# SCH_miliohn_V_1_2026-03-07.net
KiCad netlist of a schematic drawn in EasyEDA
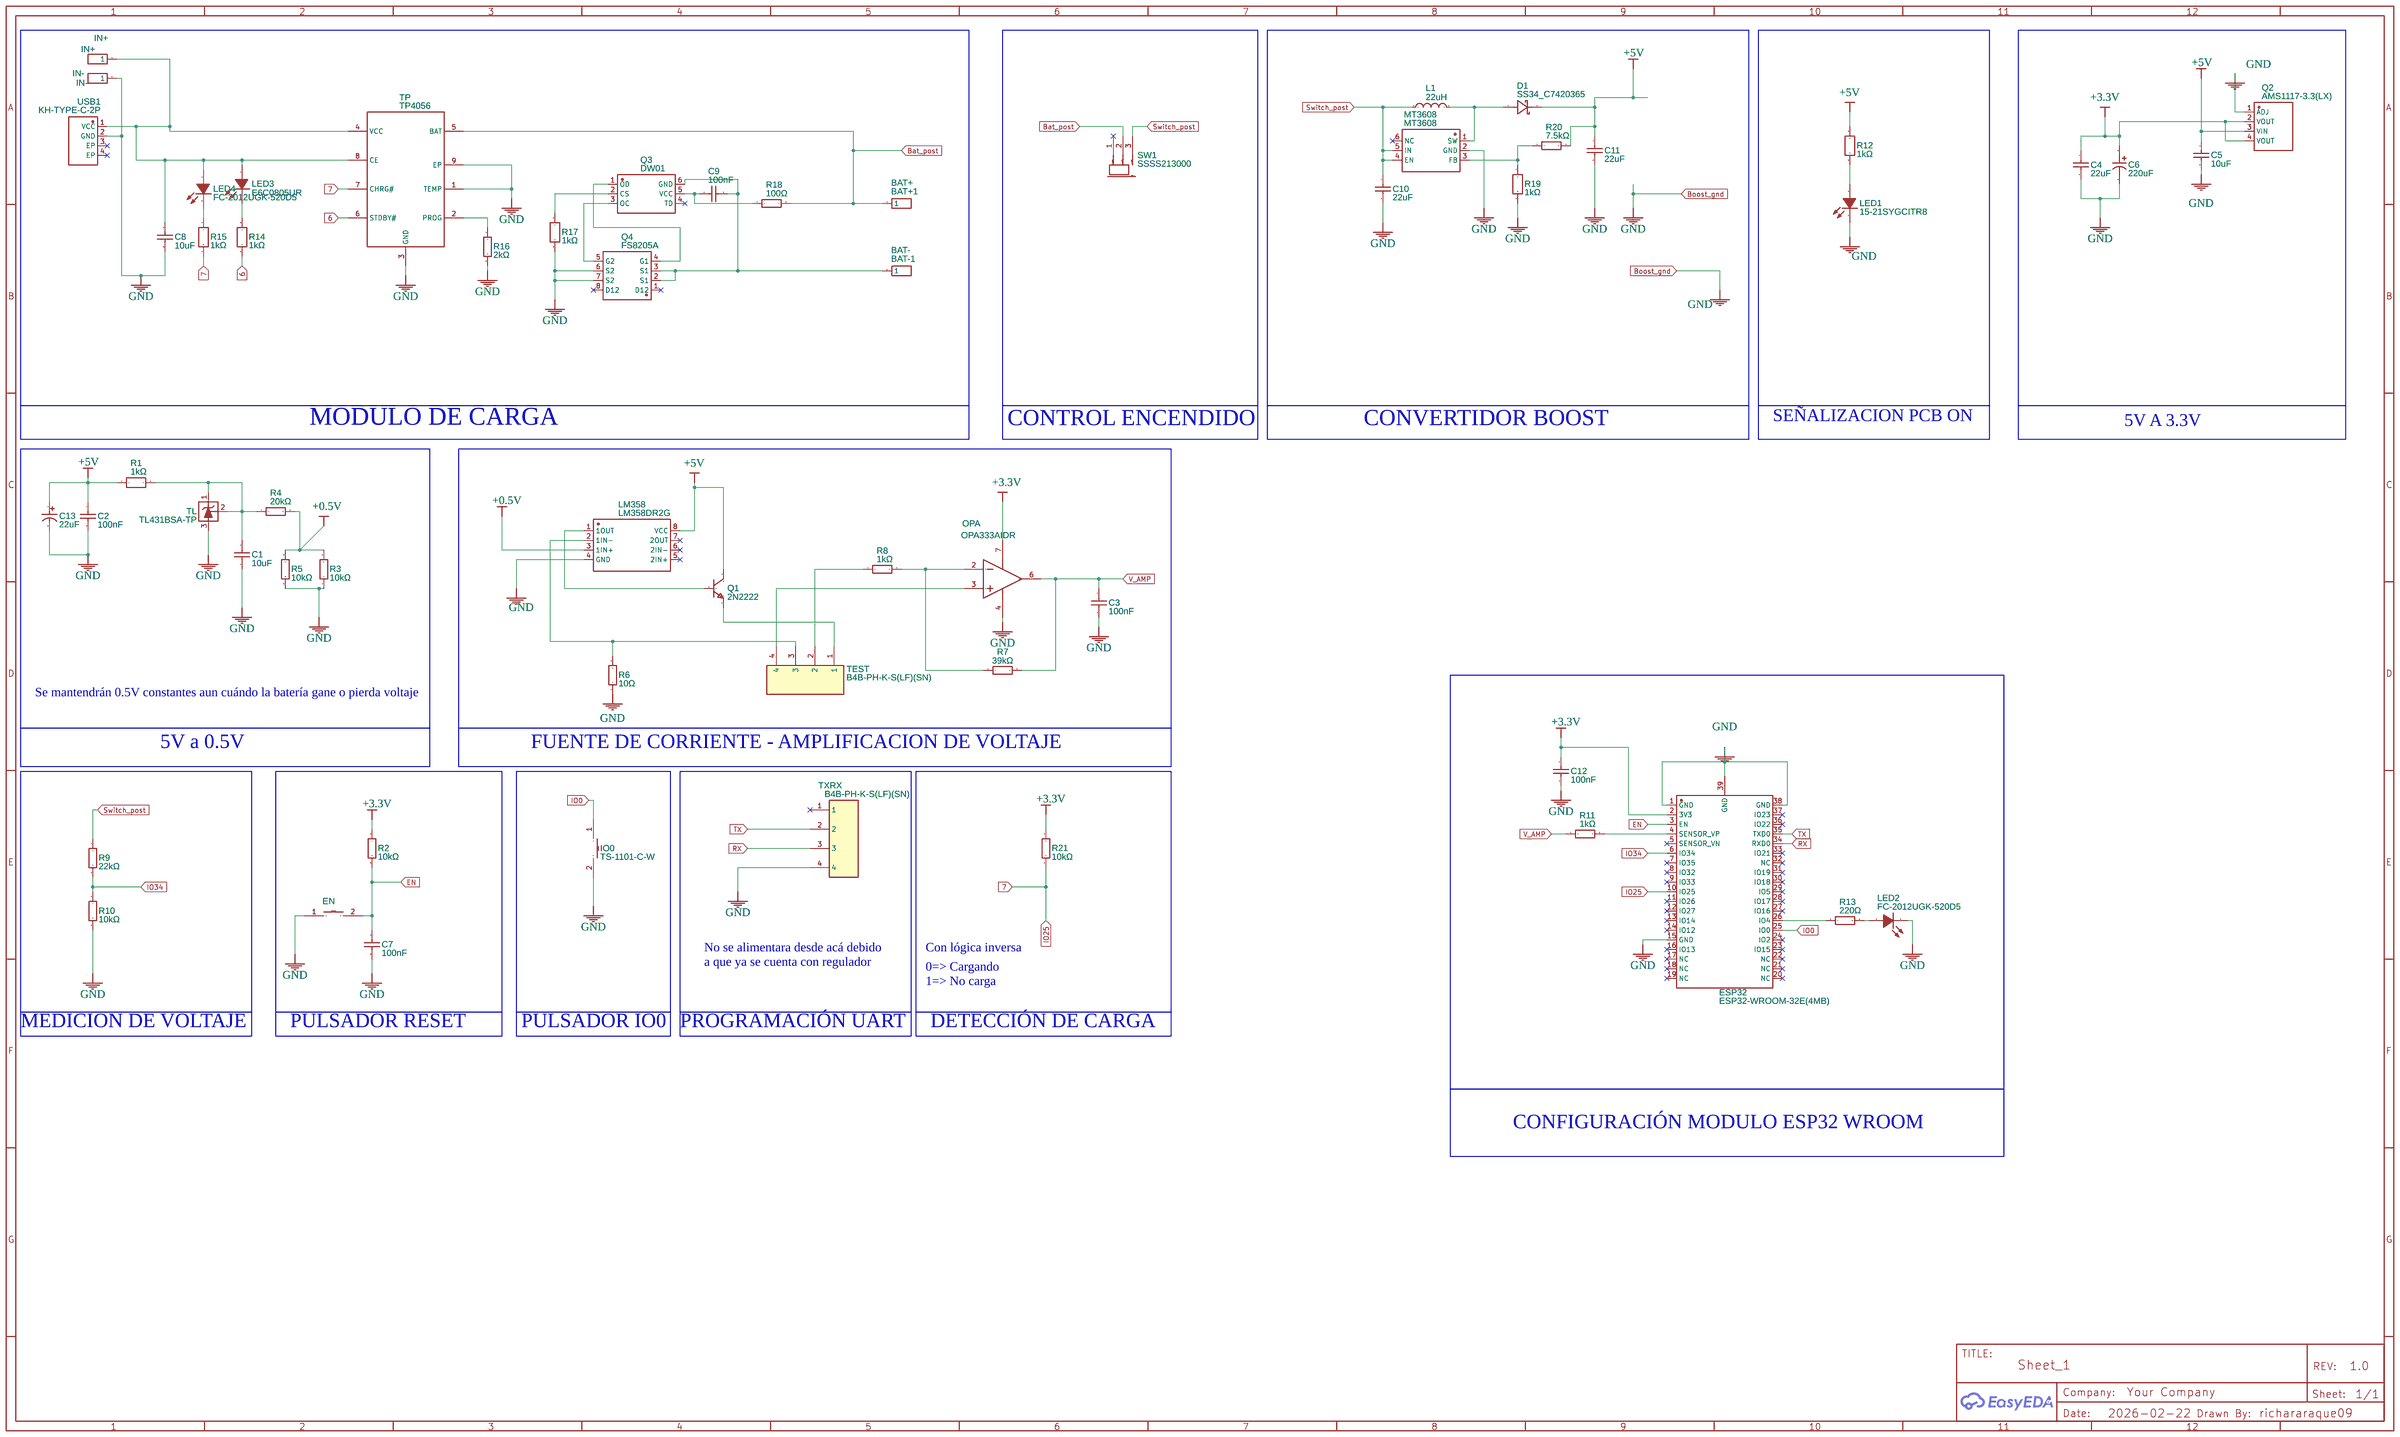
[diagram p0: schematic sheet]

(export (version "E")
  (design (tool "Eeschema 10.0.6"))
  (components
    (comp (ref "BAT+") (value "BAT+1") (libsource (lib "") (part "HDR-M-2.54_1x1_3")))
    (comp (ref "BAT-") (value "BAT-1") (libsource (lib "") (part "HDR-M-2.54_1x1")))
    (comp (ref "C1")
      (value "10uF")
      (fields
        (field (name "Manufacturer Part") "CL31A106KBHNNNE")
        (field (name "Manufacturer") "SAMSUNG(三星)")
      )
      (libsource (lib "") (part "CL31A106KBHNNNE"))
    )
    (comp (ref "C2")
      (value "100nF")
      (fields
        (field (name "Manufacturer Part") "CL31B104KBCNNNC")
        (field (name "Manufacturer") "SAMSUNG(三星)")
      )
      (libsource (lib "") (part "CL31B104KBCNNNC"))
    )
    (comp (ref "C3")
      (value "100nF")
      (fields
        (field (name "Manufacturer Part") "CL31B104KBCNNNC")
        (field (name "Manufacturer") "SAMSUNG(三星)")
      )
      (libsource (lib "") (part "CL31B104KBCNNNC"))
    )
    (comp (ref "C4")
      (value "22uF")
      (fields (field (name "Manufacturer Part") "1206X226K100NT") (field (name "Manufacturer") "FH(风华)"))
      (libsource (lib "") (part "1206X226K100NT"))
    )
    (comp (ref "C5")
      (value "10uF")
      (fields
        (field (name "Manufacturer Part") "CL31A106KBHNNNE")
        (field (name "Manufacturer") "SAMSUNG(三星)")
      )
      (libsource (lib "") (part "CL31A106KBHNNNE"))
    )
    (comp (ref "C6")
      (value "220uF")
      (fields
        (field (name "Manufacturer Part") "RVT1C221M0607 220UF 16V")
        (field (name "Manufacturer") "DMBJ(振宝佳)")
      )
      (libsource (lib "") (part "RVT1C221M0607 220UF 16V"))
    )
    (comp (ref "C7")
      (value "100nF")
      (fields
        (field (name "Manufacturer Part") "CL31B104KBCNNNC")
        (field (name "Manufacturer") "SAMSUNG(三星)")
      )
      (libsource (lib "") (part "CL31B104KBCNNNC"))
    )
    (comp (ref "C8")
      (value "10uF")
      (fields
        (field (name "Manufacturer Part") "CL31A106KBHNNNE")
        (field (name "Manufacturer") "SAMSUNG(三星)")
      )
      (libsource (lib "") (part "CL31A106KBHNNNE"))
    )
    (comp (ref "C9")
      (value "100nF")
      (fields
        (field (name "Manufacturer Part") "CL31B104KBCNNNC")
        (field (name "Manufacturer") "SAMSUNG(三星)")
      )
      (libsource (lib "") (part "CL31B104KBCNNNC_1"))
    )
    (comp (ref "C10")
      (value "22uF")
      (fields (field (name "Manufacturer Part") "1206X226K100NT") (field (name "Manufacturer") "FH(风华)"))
      (libsource (lib "") (part "1206X226K100NT"))
    )
    (comp (ref "C11")
      (value "22uF")
      (fields (field (name "Manufacturer Part") "1206X226K100NT") (field (name "Manufacturer") "FH(风华)"))
      (libsource (lib "") (part "1206X226K100NT"))
    )
    (comp (ref "C12")
      (value "100nF")
      (fields
        (field (name "Manufacturer Part") "CL31B104KBCNNNC")
        (field (name "Manufacturer") "SAMSUNG(三星)")
      )
      (libsource (lib "") (part "CL31B104KBCNNNC"))
    )
    (comp (ref "C13")
      (value "22uF")
      (fields (field (name "Manufacturer Part") "RVT1C220M0405") (field (name "Manufacturer") "HONOR(荣誉)"))
      (libsource (lib "") (part "RVT1C220M0405_C3356"))
    )
    (comp (ref "D1")
      (value "SS34_C7420365")
      (fields (field (name "Manufacturer Part") "SS34") (field (name "Manufacturer") "R+O(宏嘉诚)"))
      (libsource (lib "") (part "SS34_C7420365"))
    )
    (comp (ref "EN")
      (value "EN")
      (fields
        (field (name "Manufacturer Part") "TS-1101-C-W")
        (field (name "Manufacturer") "XKB Connectivity(中国星坤)")
      )
      (libsource (lib "") (part "TS-1101-C-W_1"))
    )
    (comp (ref "ESP32")
      (value "ESP32-WROOM-32E(4MB)")
      (fields
        (field (name "Manufacturer Part") "ESP32-WROOM-32E-N4")
        (field (name "Manufacturer") "ESPRESSIF(乐鑫)")
      )
      (libsource (lib "") (part "ESP32-WROOM-32E(4MB)"))
    )
    (comp (ref "IN+") (value "IN+") (libsource (lib "") (part "HDR-M-2.54_1x1_2")))
    (comp (ref "IN-") (value "IN-") (libsource (lib "") (part "HDR-M-2.54_1x1_1")))
    (comp (ref "IO0")
      (value "TS-1101-C-W")
      (fields (field (name "Manufacturer") "XKB Connectivity(中国星坤)"))
      (libsource (lib "") (part "TS-1101-C-W"))
    )
    (comp (ref "L1")
      (value "22uH")
      (fields (field (name "Manufacturer Part") "CD32-220K") (field (name "Manufacturer") "ceaiya(柯爱亚)"))
      (libsource (lib "") (part "CD32-220K"))
    )
    (comp (ref "LED1")
      (value "15-21SYGCITR8")
      (fields (field (name "Manufacturer Part") "KT-1206Y") (field (name "Manufacturer") "KENTO"))
      (libsource (lib "") (part "15-21SYGCITR8"))
    )
    (comp (ref "LED2")
      (value "FC-2012UGK-520D5")
      (fields (field (name "Manufacturer Part") "NCD0805G1") (field (name "Manufacturer") "国星光电"))
      (libsource (lib "") (part "FC-2012UGK-520D5"))
    )
    (comp (ref "LED3")
      (value "E6C0805UR")
      (fields (field (name "Manufacturer Part") "KT-0805R") (field (name "Manufacturer") "KENTO"))
      (libsource (lib "") (part "E6C0805UR"))
    )
    (comp (ref "LED4")
      (value "FC-2012UGK-520D5")
      (fields (field (name "Manufacturer Part") "NCD0805G1") (field (name "Manufacturer") "国星光电"))
      (libsource (lib "") (part "FC-2012UGK-520D5_1"))
    )
    (comp (ref "LM358")
      (value "LM358DR2G")
      (fields (field (name "Manufacturer") "onsemi(安森美)"))
      (libsource (lib "") (part "LM358DR2G"))
    )
    (comp (ref "MT3608")
      (value "MT3608")
      (fields (field (name "Manufacturer") "西安航天民芯"))
      (libsource (lib "") (part "MT3608"))
    )
    (comp (ref "OPA")
      (value "OPA333AIDR")
      (fields (field (name "Manufacturer") "TI(德州仪器)"))
      (libsource (lib "") (part "OPA333AIDR"))
    )
    (comp (ref "Q1")
      (value "2N2222")
      (fields (field (name "Manufacturer Part") "2N2222A") (field (name "Manufacturer") "ST(先科)"))
      (libsource (lib "") (part "2N2222"))
    )
    (comp (ref "Q2")
      (value "AMS1117-3.3(LX)")
      (fields (field (name "Manufacturer") "LX(灵星芯微)"))
      (libsource (lib "") (part "AMS1117-3.3(LX)"))
    )
    (comp (ref "Q3")
      (value "DW01")
      (fields (field (name "Manufacturer") "Hottech(合科泰)"))
      (libsource (lib "") (part "DW01"))
    )
    (comp (ref "Q4")
      (value "FS8205A")
      (fields (field (name "Manufacturer") "FORTUNE(富晶)"))
      (libsource (lib "") (part "FS8205A"))
    )
    (comp (ref "R1")
      (value "1kΩ")
      (fields (field (name "Manufacturer Part") "SCR1206J1K") (field (name "Manufacturer") "VO(翔胜)"))
      (libsource (lib "") (part "SCR1206J1K_1"))
    )
    (comp (ref "R2")
      (value "10kΩ")
      (fields
        (field (name "Manufacturer Part") "1206W4F1002T5E")
        (field (name "Manufacturer") "UNI-ROYAL(厚声)")
      )
      (libsource (lib "") (part "1206W4F1002T5E"))
    )
    (comp (ref "R3")
      (value "10kΩ")
      (fields
        (field (name "Manufacturer Part") "1206W4F1002T5E")
        (field (name "Manufacturer") "UNI-ROYAL(厚声)")
      )
      (libsource (lib "") (part "1206W4F1002T5E_1"))
    )
    (comp (ref "R4")
      (value "20kΩ")
      (fields
        (field (name "Manufacturer Part") "0805W8F2002T5E")
        (field (name "Manufacturer") "UNI-ROYAL(厚声)")
      )
      (libsource (lib "") (part "0805W8F2002T5E"))
    )
    (comp (ref "R5")
      (value "10kΩ")
      (fields
        (field (name "Manufacturer Part") "1206W4F1002T5E")
        (field (name "Manufacturer") "UNI-ROYAL(厚声)")
      )
      (libsource (lib "") (part "1206W4F1002T5E"))
    )
    (comp (ref "R6")
      (value "10Ω")
      (fields
        (field (name "Manufacturer Part") "1206W4F100JT5E")
        (field (name "Manufacturer") "UNI-ROYAL(厚声)")
      )
      (libsource (lib "") (part "1206W4F100JT5E"))
    )
    (comp (ref "R7")
      (value "39kΩ")
      (fields
        (field (name "Manufacturer Part") "1206W4F3902T5E")
        (field (name "Manufacturer") "UNI-ROYAL(厚声)")
      )
      (libsource (lib "") (part "1206W4F3902T5E"))
    )
    (comp (ref "R8")
      (value "1kΩ")
      (fields
        (field (name "Manufacturer Part") "1206W4J0102T5E")
        (field (name "Manufacturer") "UNI-ROYAL(厚声)")
      )
      (libsource (lib "") (part "1206W4J0102T5E"))
    )
    (comp (ref "R9")
      (value "22kΩ")
      (fields
        (field (name "Manufacturer Part") "1206W4F2202T5E")
        (field (name "Manufacturer") "UNI-ROYAL(厚声)")
      )
      (libsource (lib "") (part "1206W4F2202T5E"))
    )
    (comp (ref "R10")
      (value "10kΩ")
      (fields
        (field (name "Manufacturer Part") "1206W4F1002T5E")
        (field (name "Manufacturer") "UNI-ROYAL(厚声)")
      )
      (libsource (lib "") (part "1206W4F1002T5E"))
    )
    (comp (ref "R11")
      (value "1kΩ")
      (fields
        (field (name "Manufacturer Part") "1206W4J0102T5E")
        (field (name "Manufacturer") "UNI-ROYAL(厚声)")
      )
      (libsource (lib "") (part "1206W4J0102T5E"))
    )
    (comp (ref "R12")
      (value "1kΩ")
      (fields (field (name "Manufacturer Part") "SCR1206J1K") (field (name "Manufacturer") "VO(翔胜)"))
      (libsource (lib "") (part "SCR1206J1K_2"))
    )
    (comp (ref "R13")
      (value "220Ω")
      (fields
        (field (name "Manufacturer Part") "1206W4F2200T5E")
        (field (name "Manufacturer") "UNI-ROYAL(厚声)")
      )
      (libsource (lib "") (part "1206W4F2200T5E"))
    )
    (comp (ref "R14")
      (value "1kΩ")
      (fields (field (name "Manufacturer Part") "SCR1206J1K") (field (name "Manufacturer") "VO(翔胜)"))
      (libsource (lib "") (part "SCR1206J1K"))
    )
    (comp (ref "R15")
      (value "1kΩ")
      (fields (field (name "Manufacturer Part") "SCR1206J1K") (field (name "Manufacturer") "VO(翔胜)"))
      (libsource (lib "") (part "SCR1206J1K"))
    )
    (comp (ref "R16")
      (value "2kΩ")
      (fields
        (field (name "Manufacturer Part") "0805W8J0202T5E")
        (field (name "Manufacturer") "UNI-ROYAL(厚声)")
      )
      (libsource (lib "") (part "0805W8J0202T5E"))
    )
    (comp (ref "R17")
      (value "1kΩ")
      (fields (field (name "Manufacturer Part") "SCR1206J1K") (field (name "Manufacturer") "VO(翔胜)"))
      (libsource (lib "") (part "SCR1206J1K"))
    )
    (comp (ref "R18")
      (value "100Ω")
      (fields
        (field (name "Manufacturer Part") "0805W8F1000T5E")
        (field (name "Manufacturer") "UNI-ROYAL(厚声)")
      )
      (libsource (lib "") (part "0805W8F1000T5E"))
    )
    (comp (ref "R19")
      (value "1kΩ")
      (fields (field (name "Manufacturer Part") "SCR1206J1K") (field (name "Manufacturer") "VO(翔胜)"))
      (libsource (lib "") (part "SCR1206J1K"))
    )
    (comp (ref "R20")
      (value "7.5kΩ")
      (fields
        (field (name "Manufacturer Part") "0805W8F7501T5E")
        (field (name "Manufacturer") "UNI-ROYAL(厚声)")
      )
      (libsource (lib "") (part "0805W8F7501T5E"))
    )
    (comp (ref "R21")
      (value "10kΩ")
      (fields
        (field (name "Manufacturer Part") "1206W4F1002T5E")
        (field (name "Manufacturer") "UNI-ROYAL(厚声)")
      )
      (libsource (lib "") (part "1206W4F1002T5E_1"))
    )
    (comp (ref "SW1")
      (value "SSSS213000")
      (fields (field (name "Manufacturer") "ALPSALPINE(阿尔卑斯阿尔派)"))
      (libsource (lib "") (part "SSSS213000"))
    )
    (comp (ref "TEST")
      (value "B4B-PH-K-S(LF)(SN)")
      (fields (field (name "Manufacturer") "JST"))
      (libsource (lib "") (part "B4B-PH-K-S(LF)(SN)_1"))
    )
    (comp (ref "TL")
      (value "TL431BSA-TP")
      (fields (field (name "Manufacturer") "TECH PUBLIC(台舟)"))
      (libsource (lib "") (part "TL431BSA-TP"))
    )
    (comp (ref "TP")
      (value "TP4056")
      (fields
        (field (name "Manufacturer Part") "TP4056-42-ESOP8")
        (field (name "Manufacturer") "TOPPOWER(南京拓微)")
      )
      (libsource (lib "") (part "TP4056"))
    )
    (comp (ref "TXRX")
      (value "B4B-PH-K-S(LF)(SN)")
      (fields (field (name "Manufacturer") "JST"))
      (libsource (lib "") (part "B4B-PH-K-S(LF)(SN)"))
    )
    (comp (ref "USB1")
      (value "KH-TYPE-C-2P")
      (fields (field (name "Manufacturer") "kinghelm(金航标)"))
      (libsource (lib "") (part "KH-TYPE-C-2P"))
    )
  )
  (nets
    (net (code "1") (name "+0.5V") (class "Default")
      (node (ref "LM358") (pin "3") (pinfunction "1IN+_3") (pintype "unspecified"))
      (node (ref "R3") (pin "2") (pinfunction "2_2") (pintype "input"))
      (node (ref "R4") (pin "2") (pinfunction "2_2") (pintype "input"))
      (node (ref "R5") (pin "1") (pinfunction "1_1") (pintype "input"))
    )
    (net (code "2") (name "+3.3V") (class "Default")
      (node (ref "C12") (pin "1") (pinfunction "1_1") (pintype "input"))
      (node (ref "C4") (pin "1") (pinfunction "1_1") (pintype "input"))
      (node (ref "C6") (pin "1") (pinfunction "1_1") (pintype "input"))
      (node (ref "ESP32") (pin "2") (pinfunction "3V3_2") (pintype "unspecified"))
      (node (ref "OPA") (pin "7") (pinfunction "V+_7") (pintype "passive"))
      (node (ref "Q2") (pin "2") (pinfunction "VOUT_2") (pintype "unspecified"))
      (node (ref "Q2") (pin "4") (pinfunction "VOUT_4") (pintype "unspecified"))
      (node (ref "R2") (pin "1") (pinfunction "1_1") (pintype "input"))
      (node (ref "R21") (pin "2") (pinfunction "2_2") (pintype "input"))
    )
    (net (code "3") (name "+5V") (class "Default")
      (node (ref "C11") (pin "1") (pinfunction "1_1") (pintype "input"))
      (node (ref "C13") (pin "1") (pinfunction "1_1") (pintype "input"))
      (node (ref "C2") (pin "1") (pinfunction "1_1") (pintype "input"))
      (node (ref "C5") (pin "1") (pinfunction "1_1") (pintype "input"))
      (node (ref "D1") (pin "2") (pinfunction "K_2") (pintype "unspecified"))
      (node (ref "LM358") (pin "8") (pinfunction "VCC_8") (pintype "unspecified"))
      (node (ref "Q1") (pin "3") (pinfunction "C_3") (pintype "unspecified"))
      (node (ref "Q2") (pin "3") (pinfunction "VIN_3") (pintype "unspecified"))
      (node (ref "R1") (pin "1") (pinfunction "1_1") (pintype "unspecified"))
      (node (ref "R12") (pin "2") (pinfunction "2_2") (pintype "unspecified"))
      (node (ref "R20") (pin "2") (pinfunction "2_2") (pintype "input"))
    )
    (net (code "4") (name "6") (class "Default")
      (node (ref "R14") (pin "2") (pinfunction "2_2") (pintype "unspecified"))
      (node (ref "TP") (pin "6") (pinfunction "STDBY#_6") (pintype "unspecified"))
    )
    (net (code "5") (name "7") (class "Default")
      (node (ref "ESP32") (pin "10") (pinfunction "IO25_10") (pintype "unspecified"))
      (node (ref "R15") (pin "2") (pinfunction "2_2") (pintype "unspecified"))
      (node (ref "R21") (pin "1") (pinfunction "1_1") (pintype "input"))
      (node (ref "TP") (pin "7") (pinfunction "CHRG#_7") (pintype "unspecified"))
    )
    (net (code "6") (name "Bat_post") (class "Default")
      (node (ref "BAT+") (pin "1") (pinfunction "1_1") (pintype "input"))
      (node (ref "R18") (pin "2") (pinfunction "2_2") (pintype "input"))
      (node (ref "SW1") (pin "2") (pinfunction "2_2") (pintype "unspecified"))
      (node (ref "TP") (pin "5") (pinfunction "BAT_5") (pintype "unspecified"))
    )
    (net (code "7") (name "Boost_gnd") (class "Default")
      (node (ref "C1") (pin "2") (pinfunction "2_2") (pintype "input"))
      (node (ref "C10") (pin "2") (pinfunction "2_2") (pintype "input"))
      (node (ref "C11") (pin "2") (pinfunction "2_2") (pintype "input"))
      (node (ref "C12") (pin "2") (pinfunction "2_2") (pintype "input"))
      (node (ref "C13") (pin "2") (pinfunction "2_2") (pintype "input"))
      (node (ref "C2") (pin "2") (pinfunction "2_2") (pintype "input"))
      (node (ref "C3") (pin "2") (pinfunction "2_2") (pintype "input"))
      (node (ref "C4") (pin "2") (pinfunction "2_2") (pintype "input"))
      (node (ref "C5") (pin "2") (pinfunction "2_2") (pintype "input"))
      (node (ref "C6") (pin "2") (pinfunction "2_2") (pintype "input"))
      (node (ref "C7") (pin "2") (pinfunction "2_2") (pintype "input"))
      (node (ref "C8") (pin "2") (pinfunction "2_2") (pintype "input"))
      (node (ref "EN") (pin "1") (pinfunction "1_1") (pintype "unspecified"))
      (node (ref "ESP32") (pin "1") (pinfunction "GND_1") (pintype "unspecified"))
      (node (ref "ESP32") (pin "15") (pinfunction "GND_15") (pintype "unspecified"))
      (node (ref "ESP32") (pin "38") (pinfunction "GND_38") (pintype "unspecified"))
      (node (ref "ESP32") (pin "39") (pinfunction "GND_39") (pintype "unspecified"))
      (node (ref "IN-") (pin "1") (pinfunction "1_1") (pintype "input"))
      (node (ref "IO0") (pin "2") (pinfunction "2_2") (pintype "unspecified"))
      (node (ref "LED1") (pin "1") (pinfunction "-_1") (pintype "unspecified"))
      (node (ref "LED2") (pin "2") (pinfunction "K_2") (pintype "unspecified"))
      (node (ref "LM358") (pin "4") (pinfunction "GND_4") (pintype "unspecified"))
      (node (ref "MT3608") (pin "2") (pinfunction "GND_2") (pintype "unspecified"))
      (node (ref "OPA") (pin "4") (pinfunction "V-_4") (pintype "passive"))
      (node (ref "Q2") (pin "1") (pinfunction "ADJ_1") (pintype "unspecified"))
      (node (ref "Q4") (pin "6") (pinfunction "S2_6") (pintype "unspecified"))
      (node (ref "Q4") (pin "7") (pinfunction "S2_7") (pintype "unspecified"))
      (node (ref "R10") (pin "2") (pinfunction "2_2") (pintype "input"))
      (node (ref "R16") (pin "2") (pinfunction "2_2") (pintype "input"))
      (node (ref "R17") (pin "2") (pinfunction "2_2") (pintype "unspecified"))
      (node (ref "R19") (pin "2") (pinfunction "2_2") (pintype "unspecified"))
      (node (ref "R3") (pin "1") (pinfunction "1_1") (pintype "input"))
      (node (ref "R5") (pin "2") (pinfunction "2_2") (pintype "input"))
      (node (ref "R6") (pin "1") (pinfunction "1_1") (pintype "input"))
      (node (ref "TL") (pin "3") (pinfunction "A_3") (pintype "unspecified"))
      (node (ref "TP") (pin "1") (pinfunction "TEMP_1") (pintype "unspecified"))
      (node (ref "TP") (pin "3") (pinfunction "GND_3") (pintype "unspecified"))
      (node (ref "TP") (pin "9") (pinfunction "EP_9") (pintype "unspecified"))
      (node (ref "TXRX") (pin "4") (pinfunction "4_4") (pintype "input"))
      (node (ref "USB1") (pin "2") (pinfunction "GND_2") (pintype "unspecified"))
    )
    (net (code "8") (name "EN") (class "Default")
      (node (ref "C7") (pin "1") (pinfunction "1_1") (pintype "input"))
      (node (ref "EN") (pin "2") (pinfunction "2_2") (pintype "unspecified"))
      (node (ref "ESP32") (pin "3") (pinfunction "EN_3") (pintype "unspecified"))
      (node (ref "R2") (pin "2") (pinfunction "2_2") (pintype "input"))
    )
    (net (code "9") (name "IO0") (class "Default")
      (node (ref "ESP32") (pin "25") (pinfunction "IO0_25") (pintype "unspecified"))
      (node (ref "IO0") (pin "1") (pinfunction "1_1") (pintype "unspecified"))
    )
    (net (code "10") (name "IO34") (class "Default")
      (node (ref "ESP32") (pin "6") (pinfunction "IO34_6") (pintype "unspecified"))
      (node (ref "R10") (pin "1") (pinfunction "1_1") (pintype "input"))
      (node (ref "R9") (pin "2") (pinfunction "2_2") (pintype "input"))
    )
    (net (code "11") (name "Net-(D1-A)") (class "Default")
      (node (ref "D1") (pin "1") (pinfunction "A_1") (pintype "unspecified"))
      (node (ref "L1") (pin "1") (pinfunction "1_1") (pintype "unspecified"))
      (node (ref "MT3608") (pin "1") (pinfunction "SW_1") (pintype "unspecified"))
    )
    (net (code "12") (name "Net-(ESP32-IO4)") (class "Default")
      (node (ref "ESP32") (pin "26") (pinfunction "IO4_26") (pintype "unspecified"))
      (node (ref "R13") (pin "1") (pinfunction "1_1") (pintype "input"))
    )
    (net (code "13") (name "Net-(ESP32-SENSOR_VP)") (class "Default")
      (node (ref "ESP32") (pin "4") (pinfunction "SENSOR_VP_4") (pintype "unspecified"))
      (node (ref "R11") (pin "2") (pinfunction "2_2") (pintype "input"))
    )
    (net (code "14") (name "Net-(LED1-+)") (class "Default")
      (node (ref "LED1") (pin "2") (pinfunction "+_2") (pintype "unspecified"))
      (node (ref "R12") (pin "1") (pinfunction "1_1") (pintype "unspecified"))
    )
    (net (code "15") (name "Net-(LED2-A)") (class "Default")
      (node (ref "LED2") (pin "1") (pinfunction "A_1") (pintype "unspecified"))
      (node (ref "R13") (pin "2") (pinfunction "2_2") (pintype "input"))
    )
    (net (code "16") (name "Net-(LED3-A)") (class "Default")
      (node (ref "C8") (pin "1") (pinfunction "1_1") (pintype "input"))
      (node (ref "IN+") (pin "1") (pinfunction "1_1") (pintype "input"))
      (node (ref "LED3") (pin "1") (pinfunction "A_1") (pintype "unspecified"))
      (node (ref "LED4") (pin "1") (pinfunction "A_1") (pintype "unspecified"))
      (node (ref "TP") (pin "4") (pinfunction "VCC_4") (pintype "unspecified"))
      (node (ref "TP") (pin "8") (pinfunction "CE_8") (pintype "unspecified"))
      (node (ref "USB1") (pin "1") (pinfunction "VCC_1") (pintype "unspecified"))
    )
    (net (code "17") (name "Net-(LED3-K)") (class "Default")
      (node (ref "LED3") (pin "2") (pinfunction "K_2") (pintype "unspecified"))
      (node (ref "R14") (pin "1") (pinfunction "1_1") (pintype "unspecified"))
    )
    (net (code "18") (name "Net-(LED4-K)") (class "Default")
      (node (ref "LED4") (pin "2") (pinfunction "K_2") (pintype "unspecified"))
      (node (ref "R15") (pin "1") (pinfunction "1_1") (pintype "unspecified"))
    )
    (net (code "19") (name "Net-(LM358-1IN-)") (class "Default")
      (node (ref "LM358") (pin "2") (pinfunction "1IN-_2") (pintype "unspecified"))
      (node (ref "R6") (pin "2") (pinfunction "2_2") (pintype "input"))
      (node (ref "TEST") (pin "3") (pinfunction "3_3") (pintype "input"))
    )
    (net (code "20") (name "Net-(LM358-1OUT)") (class "Default")
      (node (ref "LM358") (pin "1") (pinfunction "1OUT_1") (pintype "unspecified"))
      (node (ref "Q1") (pin "2") (pinfunction "B_2") (pintype "unspecified"))
    )
    (net (code "21") (name "Net-(MT3608-FB)") (class "Default")
      (node (ref "MT3608") (pin "3") (pinfunction "FB_3") (pintype "unspecified"))
      (node (ref "R19") (pin "1") (pinfunction "1_1") (pintype "unspecified"))
      (node (ref "R20") (pin "1") (pinfunction "1_1") (pintype "input"))
    )
    (net (code "22") (name "Net-(OPA-IN+)") (class "Default")
      (node (ref "OPA") (pin "3") (pinfunction "IN+_3") (pintype "unspecified"))
      (node (ref "TEST") (pin "4") (pinfunction "4_4") (pintype "input"))
    )
    (net (code "23") (name "Net-(OPA-IN-)") (class "Default")
      (node (ref "OPA") (pin "2") (pinfunction "IN-_2") (pintype "unspecified"))
      (node (ref "R7") (pin "1") (pinfunction "1_1") (pintype "input"))
      (node (ref "R8") (pin "2") (pinfunction "2_2") (pintype "input"))
    )
    (net (code "24") (name "Net-(Q1-E)") (class "Default")
      (node (ref "Q1") (pin "1") (pinfunction "E_1") (pintype "unspecified"))
      (node (ref "TEST") (pin "1") (pinfunction "1_1") (pintype "input"))
    )
    (net (code "25") (name "Net-(Q3-CS)") (class "Default")
      (node (ref "Q3") (pin "2") (pinfunction "CS_2") (pintype "unspecified"))
      (node (ref "R17") (pin "1") (pinfunction "1_1") (pintype "unspecified"))
    )
    (net (code "26") (name "Net-(Q3-GND)") (class "Default")
      (node (ref "BAT-") (pin "1") (pinfunction "1_1") (pintype "input"))
      (node (ref "C9") (pin "2") (pinfunction "2_2") (pintype "input"))
      (node (ref "Q3") (pin "6") (pinfunction "GND_6") (pintype "unspecified"))
      (node (ref "Q4") (pin "2") (pinfunction "S1_2") (pintype "unspecified"))
      (node (ref "Q4") (pin "3") (pinfunction "S1_3") (pintype "unspecified"))
    )
    (net (code "27") (name "Net-(Q3-OC)") (class "Default")
      (node (ref "Q3") (pin "3") (pinfunction "OC_3") (pintype "unspecified"))
      (node (ref "Q4") (pin "5") (pinfunction "G2_5") (pintype "unspecified"))
    )
    (net (code "28") (name "Net-(Q3-OD)") (class "Default")
      (node (ref "Q3") (pin "1") (pinfunction "OD_1") (pintype "unspecified"))
      (node (ref "Q4") (pin "4") (pinfunction "G1_4") (pintype "unspecified"))
    )
    (net (code "29") (name "Net-(Q3-VCC)") (class "Default")
      (node (ref "C9") (pin "1") (pinfunction "1_1") (pintype "input"))
      (node (ref "Q3") (pin "5") (pinfunction "VCC_5") (pintype "unspecified"))
      (node (ref "R18") (pin "1") (pinfunction "1_1") (pintype "input"))
    )
    (net (code "30") (name "Net-(R8-Pad1)") (class "Default")
      (node (ref "R8") (pin "1") (pinfunction "1_1") (pintype "input"))
      (node (ref "TEST") (pin "2") (pinfunction "2_2") (pintype "input"))
    )
    (net (code "31") (name "Net-(TL-K)") (class "Default")
      (node (ref "C1") (pin "1") (pinfunction "1_1") (pintype "input"))
      (node (ref "R1") (pin "2") (pinfunction "2_2") (pintype "unspecified"))
      (node (ref "R4") (pin "1") (pinfunction "1_1") (pintype "input"))
      (node (ref "TL") (pin "1") (pinfunction "K_1") (pintype "unspecified"))
      (node (ref "TL") (pin "2") (pinfunction "REF_2") (pintype "unspecified"))
    )
    (net (code "32") (name "Net-(TP-PROG)") (class "Default")
      (node (ref "R16") (pin "1") (pinfunction "1_1") (pintype "input"))
      (node (ref "TP") (pin "2") (pinfunction "PROG_2") (pintype "unspecified"))
    )
    (net (code "33") (name "RX") (class "Default")
      (node (ref "ESP32") (pin "34") (pinfunction "RXD0_34") (pintype "unspecified"))
      (node (ref "TXRX") (pin "3") (pinfunction "3_3") (pintype "input"))
    )
    (net (code "34") (name "Switch_post") (class "Default")
      (node (ref "C10") (pin "1") (pinfunction "1_1") (pintype "input"))
      (node (ref "L1") (pin "2") (pinfunction "2_2") (pintype "unspecified"))
      (node (ref "MT3608") (pin "4") (pinfunction "EN_4") (pintype "unspecified"))
      (node (ref "MT3608") (pin "5") (pinfunction "IN_5") (pintype "unspecified"))
      (node (ref "R9") (pin "1") (pinfunction "1_1") (pintype "input"))
      (node (ref "SW1") (pin "3") (pinfunction "3_3") (pintype "unspecified"))
    )
    (net (code "35") (name "TX") (class "Default")
      (node (ref "ESP32") (pin "35") (pinfunction "TXD0_35") (pintype "unspecified"))
      (node (ref "TXRX") (pin "2") (pinfunction "2_2") (pintype "input"))
    )
    (net (code "36") (name "V_AMP") (class "Default")
      (node (ref "C3") (pin "1") (pinfunction "1_1") (pintype "input"))
      (node (ref "OPA") (pin "6") (pinfunction "OUT_6") (pintype "output"))
      (node (ref "R11") (pin "1") (pinfunction "1_1") (pintype "input"))
      (node (ref "R7") (pin "2") (pinfunction "2_2") (pintype "input"))
    )
    (net (code "37") (name "unconnected-(ESP32-IO2-Pad24)") (class "Default")
      (node (ref "ESP32") (pin "24") (pinfunction "IO2_24") (pintype "unspecified+no_connect"))
    )
    (net (code "38") (name "unconnected-(ESP32-IO5-Pad29)") (class "Default")
      (node (ref "ESP32") (pin "29") (pinfunction "IO5_29") (pintype "unspecified+no_connect"))
    )
    (net (code "39") (name "unconnected-(ESP32-IO12-Pad14)") (class "Default")
      (node (ref "ESP32") (pin "14") (pinfunction "IO12_14") (pintype "unspecified+no_connect"))
    )
    (net (code "40") (name "unconnected-(ESP32-IO13-Pad16)") (class "Default")
      (node (ref "ESP32") (pin "16") (pinfunction "IO13_16") (pintype "unspecified+no_connect"))
    )
    (net (code "41") (name "unconnected-(ESP32-IO14-Pad13)") (class "Default")
      (node (ref "ESP32") (pin "13") (pinfunction "IO14_13") (pintype "unspecified+no_connect"))
    )
    (net (code "42") (name "unconnected-(ESP32-IO15-Pad23)") (class "Default")
      (node (ref "ESP32") (pin "23") (pinfunction "IO15_23") (pintype "unspecified+no_connect"))
    )
    (net (code "43") (name "unconnected-(ESP32-IO16-Pad27)") (class "Default")
      (node (ref "ESP32") (pin "27") (pinfunction "IO16_27") (pintype "unspecified+no_connect"))
    )
    (net (code "44") (name "unconnected-(ESP32-IO17-Pad28)") (class "Default")
      (node (ref "ESP32") (pin "28") (pinfunction "IO17_28") (pintype "unspecified+no_connect"))
    )
    (net (code "45") (name "unconnected-(ESP32-IO18-Pad30)") (class "Default")
      (node (ref "ESP32") (pin "30") (pinfunction "IO18_30") (pintype "unspecified+no_connect"))
    )
    (net (code "46") (name "unconnected-(ESP32-IO19-Pad31)") (class "Default")
      (node (ref "ESP32") (pin "31") (pinfunction "IO19_31") (pintype "unspecified+no_connect"))
    )
    (net (code "47") (name "unconnected-(ESP32-IO21-Pad33)") (class "Default")
      (node (ref "ESP32") (pin "33") (pinfunction "IO21_33") (pintype "unspecified+no_connect"))
    )
    (net (code "48") (name "unconnected-(ESP32-IO22-Pad36)") (class "Default")
      (node (ref "ESP32") (pin "36") (pinfunction "IO22_36") (pintype "unspecified+no_connect"))
    )
    (net (code "49") (name "unconnected-(ESP32-IO23-Pad37)") (class "Default")
      (node (ref "ESP32") (pin "37") (pinfunction "IO23_37") (pintype "unspecified+no_connect"))
    )
    (net (code "50") (name "unconnected-(ESP32-IO26-Pad11)") (class "Default")
      (node (ref "ESP32") (pin "11") (pinfunction "IO26_11") (pintype "unspecified+no_connect"))
    )
    (net (code "51") (name "unconnected-(ESP32-IO27-Pad12)") (class "Default")
      (node (ref "ESP32") (pin "12") (pinfunction "IO27_12") (pintype "unspecified+no_connect"))
    )
    (net (code "52") (name "unconnected-(ESP32-IO32-Pad8)") (class "Default")
      (node (ref "ESP32") (pin "8") (pinfunction "IO32_8") (pintype "unspecified+no_connect"))
    )
    (net (code "53") (name "unconnected-(ESP32-IO33-Pad9)") (class "Default")
      (node (ref "ESP32") (pin "9") (pinfunction "IO33_9") (pintype "unspecified+no_connect"))
    )
    (net (code "54") (name "unconnected-(ESP32-IO35-Pad7)") (class "Default")
      (node (ref "ESP32") (pin "7") (pinfunction "IO35_7") (pintype "unspecified+no_connect"))
    )
    (net (code "55") (name "unconnected-(ESP32-NC-Pad17)") (class "Default")
      (node (ref "ESP32") (pin "17") (pinfunction "NC_17") (pintype "unspecified+no_connect"))
    )
    (net (code "56") (name "unconnected-(ESP32-NC-Pad18)") (class "Default")
      (node (ref "ESP32") (pin "18") (pinfunction "NC_18") (pintype "unspecified+no_connect"))
    )
    (net (code "57") (name "unconnected-(ESP32-NC-Pad19)") (class "Default")
      (node (ref "ESP32") (pin "19") (pinfunction "NC_19") (pintype "unspecified+no_connect"))
    )
    (net (code "58") (name "unconnected-(ESP32-NC-Pad20)") (class "Default")
      (node (ref "ESP32") (pin "20") (pinfunction "NC_20") (pintype "unspecified+no_connect"))
    )
    (net (code "59") (name "unconnected-(ESP32-NC-Pad21)") (class "Default")
      (node (ref "ESP32") (pin "21") (pinfunction "NC_21") (pintype "unspecified+no_connect"))
    )
    (net (code "60") (name "unconnected-(ESP32-NC-Pad22)") (class "Default")
      (node (ref "ESP32") (pin "22") (pinfunction "NC_22") (pintype "unspecified+no_connect"))
    )
    (net (code "61") (name "unconnected-(ESP32-NC-Pad32)") (class "Default")
      (node (ref "ESP32") (pin "32") (pinfunction "NC_32") (pintype "unspecified+no_connect"))
    )
    (net (code "62") (name "unconnected-(ESP32-SENSOR_VN-Pad5)") (class "Default")
      (node (ref "ESP32") (pin "5") (pinfunction "SENSOR_VN_5") (pintype "unspecified+no_connect"))
    )
    (net (code "63") (name "unconnected-(LM358-2IN+-Pad5)") (class "Default")
      (node (ref "LM358") (pin "5") (pinfunction "2IN+_5") (pintype "unspecified+no_connect"))
    )
    (net (code "64") (name "unconnected-(LM358-2IN--Pad6)") (class "Default")
      (node (ref "LM358") (pin "6") (pinfunction "2IN-_6") (pintype "unspecified+no_connect"))
    )
    (net (code "65") (name "unconnected-(LM358-2OUT-Pad7)") (class "Default")
      (node (ref "LM358") (pin "7") (pinfunction "2OUT_7") (pintype "unspecified+no_connect"))
    )
    (net (code "66") (name "unconnected-(MT3608-NC-Pad6)") (class "Default")
      (node (ref "MT3608") (pin "6") (pinfunction "NC_6") (pintype "unspecified+no_connect"))
    )
    (net (code "67") (name "unconnected-(Q3-TD-Pad4)") (class "Default")
      (node (ref "Q3") (pin "4") (pinfunction "TD_4") (pintype "unspecified+no_connect"))
    )
    (net (code "68") (name "unconnected-(Q4-D12-Pad1)") (class "Default")
      (node (ref "Q4") (pin "1") (pinfunction "D12_1") (pintype "unspecified+no_connect"))
    )
    (net (code "69") (name "unconnected-(Q4-D12-Pad8)") (class "Default")
      (node (ref "Q4") (pin "8") (pinfunction "D12_8") (pintype "unspecified+no_connect"))
    )
    (net (code "70") (name "unconnected-(SW1-Pad1)") (class "Default")
      (node (ref "SW1") (pin "1") (pinfunction "1_1") (pintype "unspecified+no_connect"))
    )
    (net (code "71") (name "unconnected-(TXRX-Pad1)") (class "Default")
      (node (ref "TXRX") (pin "1") (pinfunction "1_1") (pintype "input+no_connect"))
    )
    (net (code "72") (name "unconnected-(USB1-EP-Pad3)") (class "Default")
      (node (ref "USB1") (pin "3") (pinfunction "EP_3") (pintype "unspecified+no_connect"))
    )
    (net (code "73") (name "unconnected-(USB1-EP-Pad4)") (class "Default")
      (node (ref "USB1") (pin "4") (pinfunction "EP_4") (pintype "unspecified+no_connect"))
    )
  )
)
